# dsl-lights.net
KiCad netlist of a schematic drawn in EAGLE
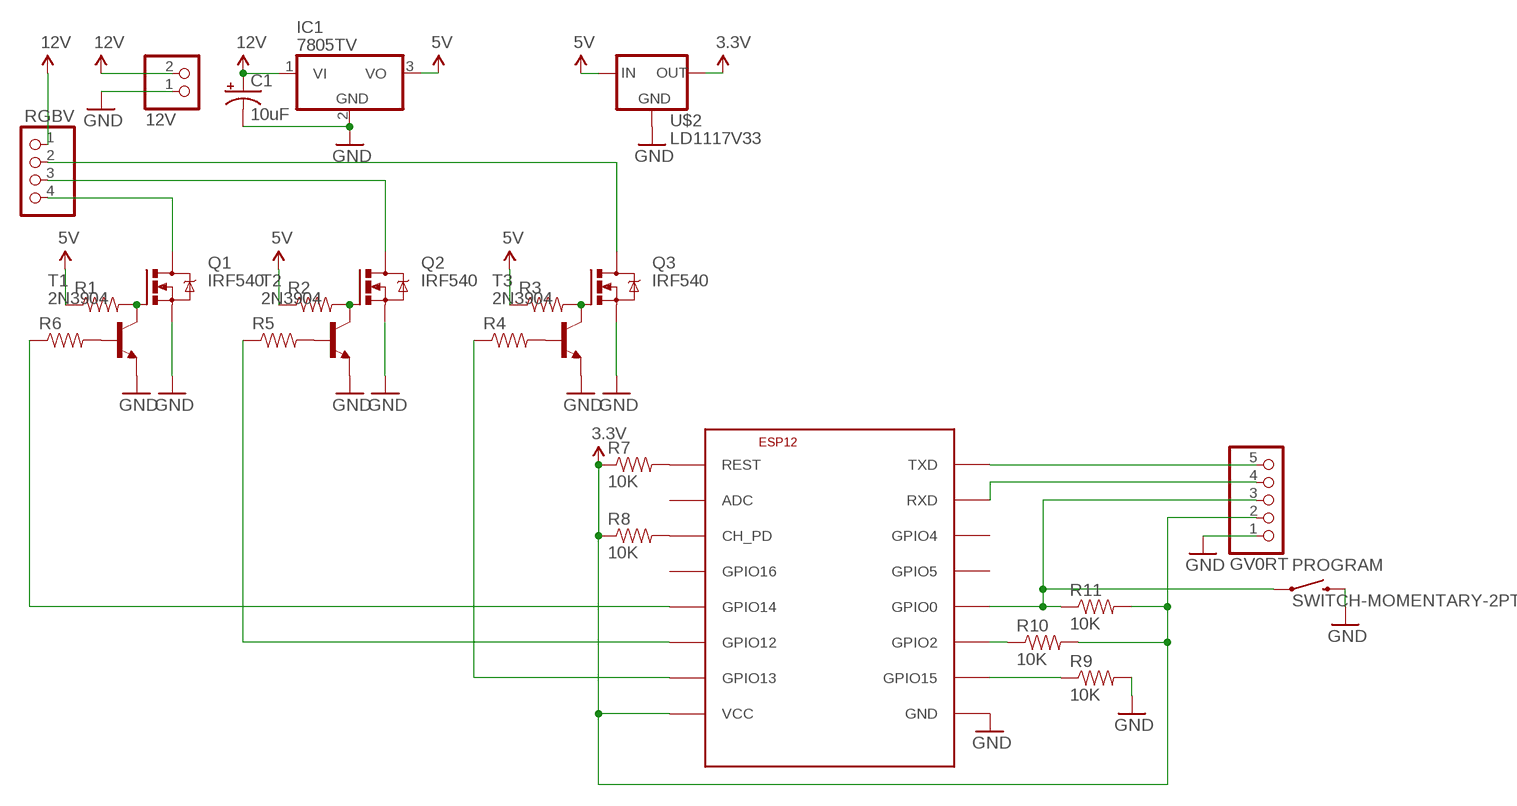
[diagram p0: schematic, sheet 1]

(export (version "E")
  (design (tool "Eeschema 10.0.6"))
  (components
    (comp (ref "12V")
      (value "HEADER-1X2")
      (footprint "eagle-import:1X02_OVAL")
      (libsource (lib "eagle-import") (part "HEADER-1X2"))
    )
    (comp (ref "C1")
      (value "10uF")
      (footprint "eagle-import:CPOL-RADIAL-100UF-25V")
      (libsource (lib "eagle-import") (part "CAP_POLPTH1"))
    )
    (comp (ref "ESP12")
      (value "ESP8266-12")
      (footprint "eagle-import:ESP-12")
      (libsource (lib "eagle-import") (part "ESP8266-12"))
    )
    (comp (ref "GV0RT")
      (value "HEADER-1X5")
      (footprint "eagle-import:1X05_OVAL")
      (libsource (lib "eagle-import") (part "HEADER-1X5"))
    )
    (comp (ref "IC1")
      (value "7805TV")
      (footprint "eagle-import:TO220V")
      (libsource (lib "eagle-import") (part "78TV05"))
    )
    (comp (ref "PROGRAM")
      (value "SWITCH-MOMENTARY-2PTH")
      (footprint "eagle-import:TACTILE-PTH")
      (libsource (lib "eagle-import") (part "SWITCH-MOMENTARY-2PTH"))
    )
    (comp (ref "Q1")
      (value "IRF540")
      (footprint "eagle-import:TO220BV")
      (libsource (lib "eagle-import") (part "IRF540"))
    )
    (comp (ref "Q2")
      (value "IRF540")
      (footprint "eagle-import:TO220BV")
      (libsource (lib "eagle-import") (part "IRF540"))
    )
    (comp (ref "Q3")
      (value "IRF540")
      (footprint "eagle-import:TO220BV")
      (libsource (lib "eagle-import") (part "IRF540"))
    )
    (comp (ref "R1")
      (value "RESISTORAXIAL-0.3")
      (footprint "eagle-import:AXIAL-0.3")
      (libsource (lib "eagle-import") (part "RESISTORAXIAL-0.3"))
    )
    (comp (ref "R2")
      (value "RESISTORAXIAL-0.3")
      (footprint "eagle-import:AXIAL-0.3")
      (libsource (lib "eagle-import") (part "RESISTORAXIAL-0.3"))
    )
    (comp (ref "R3")
      (value "RESISTORAXIAL-0.3")
      (footprint "eagle-import:AXIAL-0.3")
      (libsource (lib "eagle-import") (part "RESISTORAXIAL-0.3"))
    )
    (comp (ref "R4")
      (value "RESISTORAXIAL-0.3")
      (footprint "eagle-import:AXIAL-0.3")
      (libsource (lib "eagle-import") (part "RESISTORAXIAL-0.3"))
    )
    (comp (ref "R5")
      (value "RESISTORAXIAL-0.3")
      (footprint "eagle-import:AXIAL-0.3")
      (libsource (lib "eagle-import") (part "RESISTORAXIAL-0.3"))
    )
    (comp (ref "R6")
      (value "RESISTORAXIAL-0.3")
      (footprint "eagle-import:AXIAL-0.3")
      (libsource (lib "eagle-import") (part "RESISTORAXIAL-0.3"))
    )
    (comp (ref "R7")
      (value "10K")
      (footprint "eagle-import:AXIAL-0.3")
      (libsource (lib "eagle-import") (part "RESISTORAXIAL-0.3"))
    )
    (comp (ref "R8")
      (value "10K")
      (footprint "eagle-import:AXIAL-0.3")
      (libsource (lib "eagle-import") (part "RESISTORAXIAL-0.3"))
    )
    (comp (ref "R9")
      (value "10K")
      (footprint "eagle-import:AXIAL-0.3")
      (libsource (lib "eagle-import") (part "RESISTORAXIAL-0.3"))
    )
    (comp (ref "R10")
      (value "10K")
      (footprint "eagle-import:AXIAL-0.3")
      (libsource (lib "eagle-import") (part "RESISTORAXIAL-0.3"))
    )
    (comp (ref "R11")
      (value "10K")
      (footprint "eagle-import:AXIAL-0.3")
      (libsource (lib "eagle-import") (part "RESISTORAXIAL-0.3"))
    )
    (comp (ref "RGBV")
      (value "HEADER-1X4")
      (footprint "eagle-import:1X04_OVAL")
      (libsource (lib "eagle-import") (part "HEADER-1X4"))
    )
    (comp (ref "T1")
      (value "2N3904")
      (footprint "eagle-import:TO92")
      (libsource (lib "eagle-import") (part "2N3904"))
    )
    (comp (ref "T2")
      (value "2N3904")
      (footprint "eagle-import:TO92")
      (libsource (lib "eagle-import") (part "2N3904"))
    )
    (comp (ref "T3")
      (value "2N3904")
      (footprint "eagle-import:TO92")
      (libsource (lib "eagle-import") (part "2N3904"))
    )
    (comp (ref "U$2")
      (value "LD1117V33")
      (footprint "eagle-import:78XXL")
      (libsource (lib "eagle-import") (part "V_REG_LD1117VXX"))
    )
  )
  (nets
    (net (code "1") (name "3.3V") (class "Default")
      (node (ref "ESP12") (pin "VCC") (pinfunction "VCC_VCC") (pintype "power_in"))
      (node (ref "GV0RT") (pin "2") (pinfunction "2_2") (pintype "passive"))
      (node (ref "R10") (pin "P$2") (pinfunction "2_P$2") (pintype "passive"))
      (node (ref "R11") (pin "P$2") (pinfunction "2_P$2") (pintype "passive"))
      (node (ref "R7") (pin "P$1") (pinfunction "1_P$1") (pintype "passive"))
      (node (ref "R8") (pin "P$1") (pinfunction "1_P$1") (pintype "passive"))
      (node (ref "U$2") (pin "GND") (pinfunction "OUT_GND") (pintype "passive"))
    )
    (net (code "2") (name "5V") (class "Default")
      (node (ref "IC1") (pin "3") (pinfunction "VO_3") (pintype "passive"))
      (node (ref "R1") (pin "P$1") (pinfunction "1_P$1") (pintype "passive"))
      (node (ref "R2") (pin "P$1") (pinfunction "1_P$1") (pintype "passive"))
      (node (ref "R3") (pin "P$1") (pinfunction "1_P$1") (pintype "passive"))
      (node (ref "U$2") (pin "OUT") (pinfunction "IN_OUT") (pintype "input"))
    )
    (net (code "3") (name "12V") (class "Default")
      (node (ref "12V") (pin "2") (pinfunction "2_2") (pintype "passive"))
      (node (ref "C1") (pin "1") (pinfunction "+_1") (pintype "passive"))
      (node (ref "IC1") (pin "1") (pinfunction "VI_1") (pintype "input"))
      (node (ref "RGBV") (pin "1") (pinfunction "1_1") (pintype "passive"))
    )
    (net (code "4") (name "GND") (class "Default")
      (node (ref "12V") (pin "1") (pinfunction "1_1") (pintype "passive"))
      (node (ref "C1") (pin "2") (pinfunction "-_2") (pintype "passive"))
      (node (ref "ESP12") (pin "GND") (pinfunction "GND_GND") (pintype "power_in"))
      (node (ref "GV0RT") (pin "1") (pinfunction "1_1") (pintype "passive"))
      (node (ref "IC1") (pin "2") (pinfunction "GND_2") (pintype "passive"))
      (node (ref "PROGRAM") (pin "3") (pinfunction "2_3") (pintype "passive"))
      (node (ref "Q1") (pin "S") (pinfunction "S_S") (pintype "passive"))
      (node (ref "Q2") (pin "S") (pinfunction "S_S") (pintype "passive"))
      (node (ref "Q3") (pin "S") (pinfunction "S_S") (pintype "passive"))
      (node (ref "R9") (pin "P$2") (pinfunction "2_P$2") (pintype "passive"))
      (node (ref "T1") (pin "3") (pinfunction "E_3") (pintype "passive"))
      (node (ref "T2") (pin "3") (pinfunction "E_3") (pintype "passive"))
      (node (ref "T3") (pin "3") (pinfunction "E_3") (pintype "passive"))
      (node (ref "U$2") (pin "IN") (pinfunction "GND_IN") (pintype "input"))
    )
    (net (code "5") (name "Net-(ESP12-PadRXD)") (class "Default")
      (node (ref "ESP12") (pin "RXD") (pinfunction "RXD_RXD") (pintype "input"))
      (node (ref "GV0RT") (pin "4") (pinfunction "4_4") (pintype "passive"))
    )
    (net (code "6") (name "Net-(ESP12-PadTXD)") (class "Default")
      (node (ref "ESP12") (pin "TXD") (pinfunction "TXD_TXD") (pintype "output"))
      (node (ref "GV0RT") (pin "5") (pinfunction "5_5") (pintype "passive"))
    )
    (net (code "7") (name "Net-(Q1-PadD)") (class "Default")
      (node (ref "Q1") (pin "D") (pinfunction "D_D") (pintype "passive"))
      (node (ref "RGBV") (pin "4") (pinfunction "4_4") (pintype "passive"))
    )
    (net (code "8") (name "Net-(Q2-PadD)") (class "Default")
      (node (ref "Q2") (pin "D") (pinfunction "D_D") (pintype "passive"))
      (node (ref "RGBV") (pin "3") (pinfunction "3_3") (pintype "passive"))
    )
    (net (code "9") (name "Net-(Q3-PadD)") (class "Default")
      (node (ref "Q3") (pin "D") (pinfunction "D_D") (pintype "passive"))
      (node (ref "RGBV") (pin "2") (pinfunction "2_2") (pintype "passive"))
    )
    (net (code "10") (name "Net-(R1-2)") (class "Default")
      (node (ref "Q1") (pin "G") (pinfunction "G_G") (pintype "passive"))
      (node (ref "R1") (pin "P$2") (pinfunction "2_P$2") (pintype "passive"))
      (node (ref "T1") (pin "1") (pinfunction "C_1") (pintype "passive"))
    )
    (net (code "11") (name "Net-(R2-2)") (class "Default")
      (node (ref "Q2") (pin "G") (pinfunction "G_G") (pintype "passive"))
      (node (ref "R2") (pin "P$2") (pinfunction "2_P$2") (pintype "passive"))
      (node (ref "T2") (pin "1") (pinfunction "C_1") (pintype "passive"))
    )
    (net (code "12") (name "Net-(R3-2)") (class "Default")
      (node (ref "Q3") (pin "G") (pinfunction "G_G") (pintype "passive"))
      (node (ref "R3") (pin "P$2") (pinfunction "2_P$2") (pintype "passive"))
      (node (ref "T3") (pin "1") (pinfunction "C_1") (pintype "passive"))
    )
    (net (code "13") (name "Net-(R4-1)") (class "Default")
      (node (ref "ESP12") (pin "GPIO13") (pinfunction "GPIO13_GPIO13") (pintype "bidirectional"))
      (node (ref "R4") (pin "P$1") (pinfunction "1_P$1") (pintype "passive"))
    )
    (net (code "14") (name "Net-(R4-2)") (class "Default")
      (node (ref "R4") (pin "P$2") (pinfunction "2_P$2") (pintype "passive"))
      (node (ref "T3") (pin "2") (pinfunction "B_2") (pintype "passive"))
    )
    (net (code "15") (name "Net-(R5-1)") (class "Default")
      (node (ref "ESP12") (pin "GPIO12") (pinfunction "GPIO12_GPIO12") (pintype "bidirectional"))
      (node (ref "R5") (pin "P$1") (pinfunction "1_P$1") (pintype "passive"))
    )
    (net (code "16") (name "Net-(R5-2)") (class "Default")
      (node (ref "R5") (pin "P$2") (pinfunction "2_P$2") (pintype "passive"))
      (node (ref "T2") (pin "2") (pinfunction "B_2") (pintype "passive"))
    )
    (net (code "17") (name "Net-(R6-1)") (class "Default")
      (node (ref "ESP12") (pin "GPIO14") (pinfunction "GPIO14_GPIO14") (pintype "bidirectional"))
      (node (ref "R6") (pin "P$1") (pinfunction "1_P$1") (pintype "passive"))
    )
    (net (code "18") (name "Net-(R6-2)") (class "Default")
      (node (ref "R6") (pin "P$2") (pinfunction "2_P$2") (pintype "passive"))
      (node (ref "T1") (pin "2") (pinfunction "B_2") (pintype "passive"))
    )
    (net (code "19") (name "Net-(R7-2)") (class "Default")
      (node (ref "ESP12") (pin "REST") (pinfunction "REST_REST") (pintype "bidirectional"))
      (node (ref "R7") (pin "P$2") (pinfunction "2_P$2") (pintype "passive"))
    )
    (net (code "20") (name "Net-(R8-2)") (class "Default")
      (node (ref "ESP12") (pin "CH_PD") (pinfunction "CH_PD_CH_PD") (pintype "input"))
      (node (ref "R8") (pin "P$2") (pinfunction "2_P$2") (pintype "passive"))
    )
    (net (code "21") (name "Net-(R9-1)") (class "Default")
      (node (ref "ESP12") (pin "GPIO15") (pinfunction "GPIO15_GPIO15") (pintype "input"))
      (node (ref "R9") (pin "P$1") (pinfunction "1_P$1") (pintype "passive"))
    )
    (net (code "22") (name "Net-(R10-1)") (class "Default")
      (node (ref "ESP12") (pin "GPIO2") (pinfunction "GPIO2_GPIO2") (pintype "bidirectional"))
      (node (ref "R10") (pin "P$1") (pinfunction "1_P$1") (pintype "passive"))
    )
    (net (code "23") (name "Net-(R11-1)") (class "Default")
      (node (ref "ESP12") (pin "GPIO0") (pinfunction "GPIO0_GPIO0") (pintype "bidirectional"))
      (node (ref "GV0RT") (pin "3") (pinfunction "3_3") (pintype "passive"))
      (node (ref "PROGRAM") (pin "1") (pinfunction "1_1") (pintype "passive"))
      (node (ref "R11") (pin "P$1") (pinfunction "1_P$1") (pintype "passive"))
    )
    (net (code "24") (name "unconnected-(ESP12-PadADC)") (class "Default")
      (node (ref "ESP12") (pin "ADC") (pinfunction "ADC_ADC") (pintype "bidirectional"))
    )
    (net (code "25") (name "unconnected-(ESP12-PadGPIO4)") (class "Default")
      (node (ref "ESP12") (pin "GPIO4") (pinfunction "GPIO4_GPIO4") (pintype "bidirectional"))
    )
    (net (code "26") (name "unconnected-(ESP12-PadGPIO5)") (class "Default")
      (node (ref "ESP12") (pin "GPIO5") (pinfunction "GPIO5_GPIO5") (pintype "bidirectional"))
    )
    (net (code "27") (name "unconnected-(ESP12-PadGPIO16)") (class "Default")
      (node (ref "ESP12") (pin "GPIO16") (pinfunction "GPIO16_GPIO16") (pintype "bidirectional"))
    )
  )
)
